# MCU_RF.net
KiCad netlist of a schematic drawn in Altium Designer
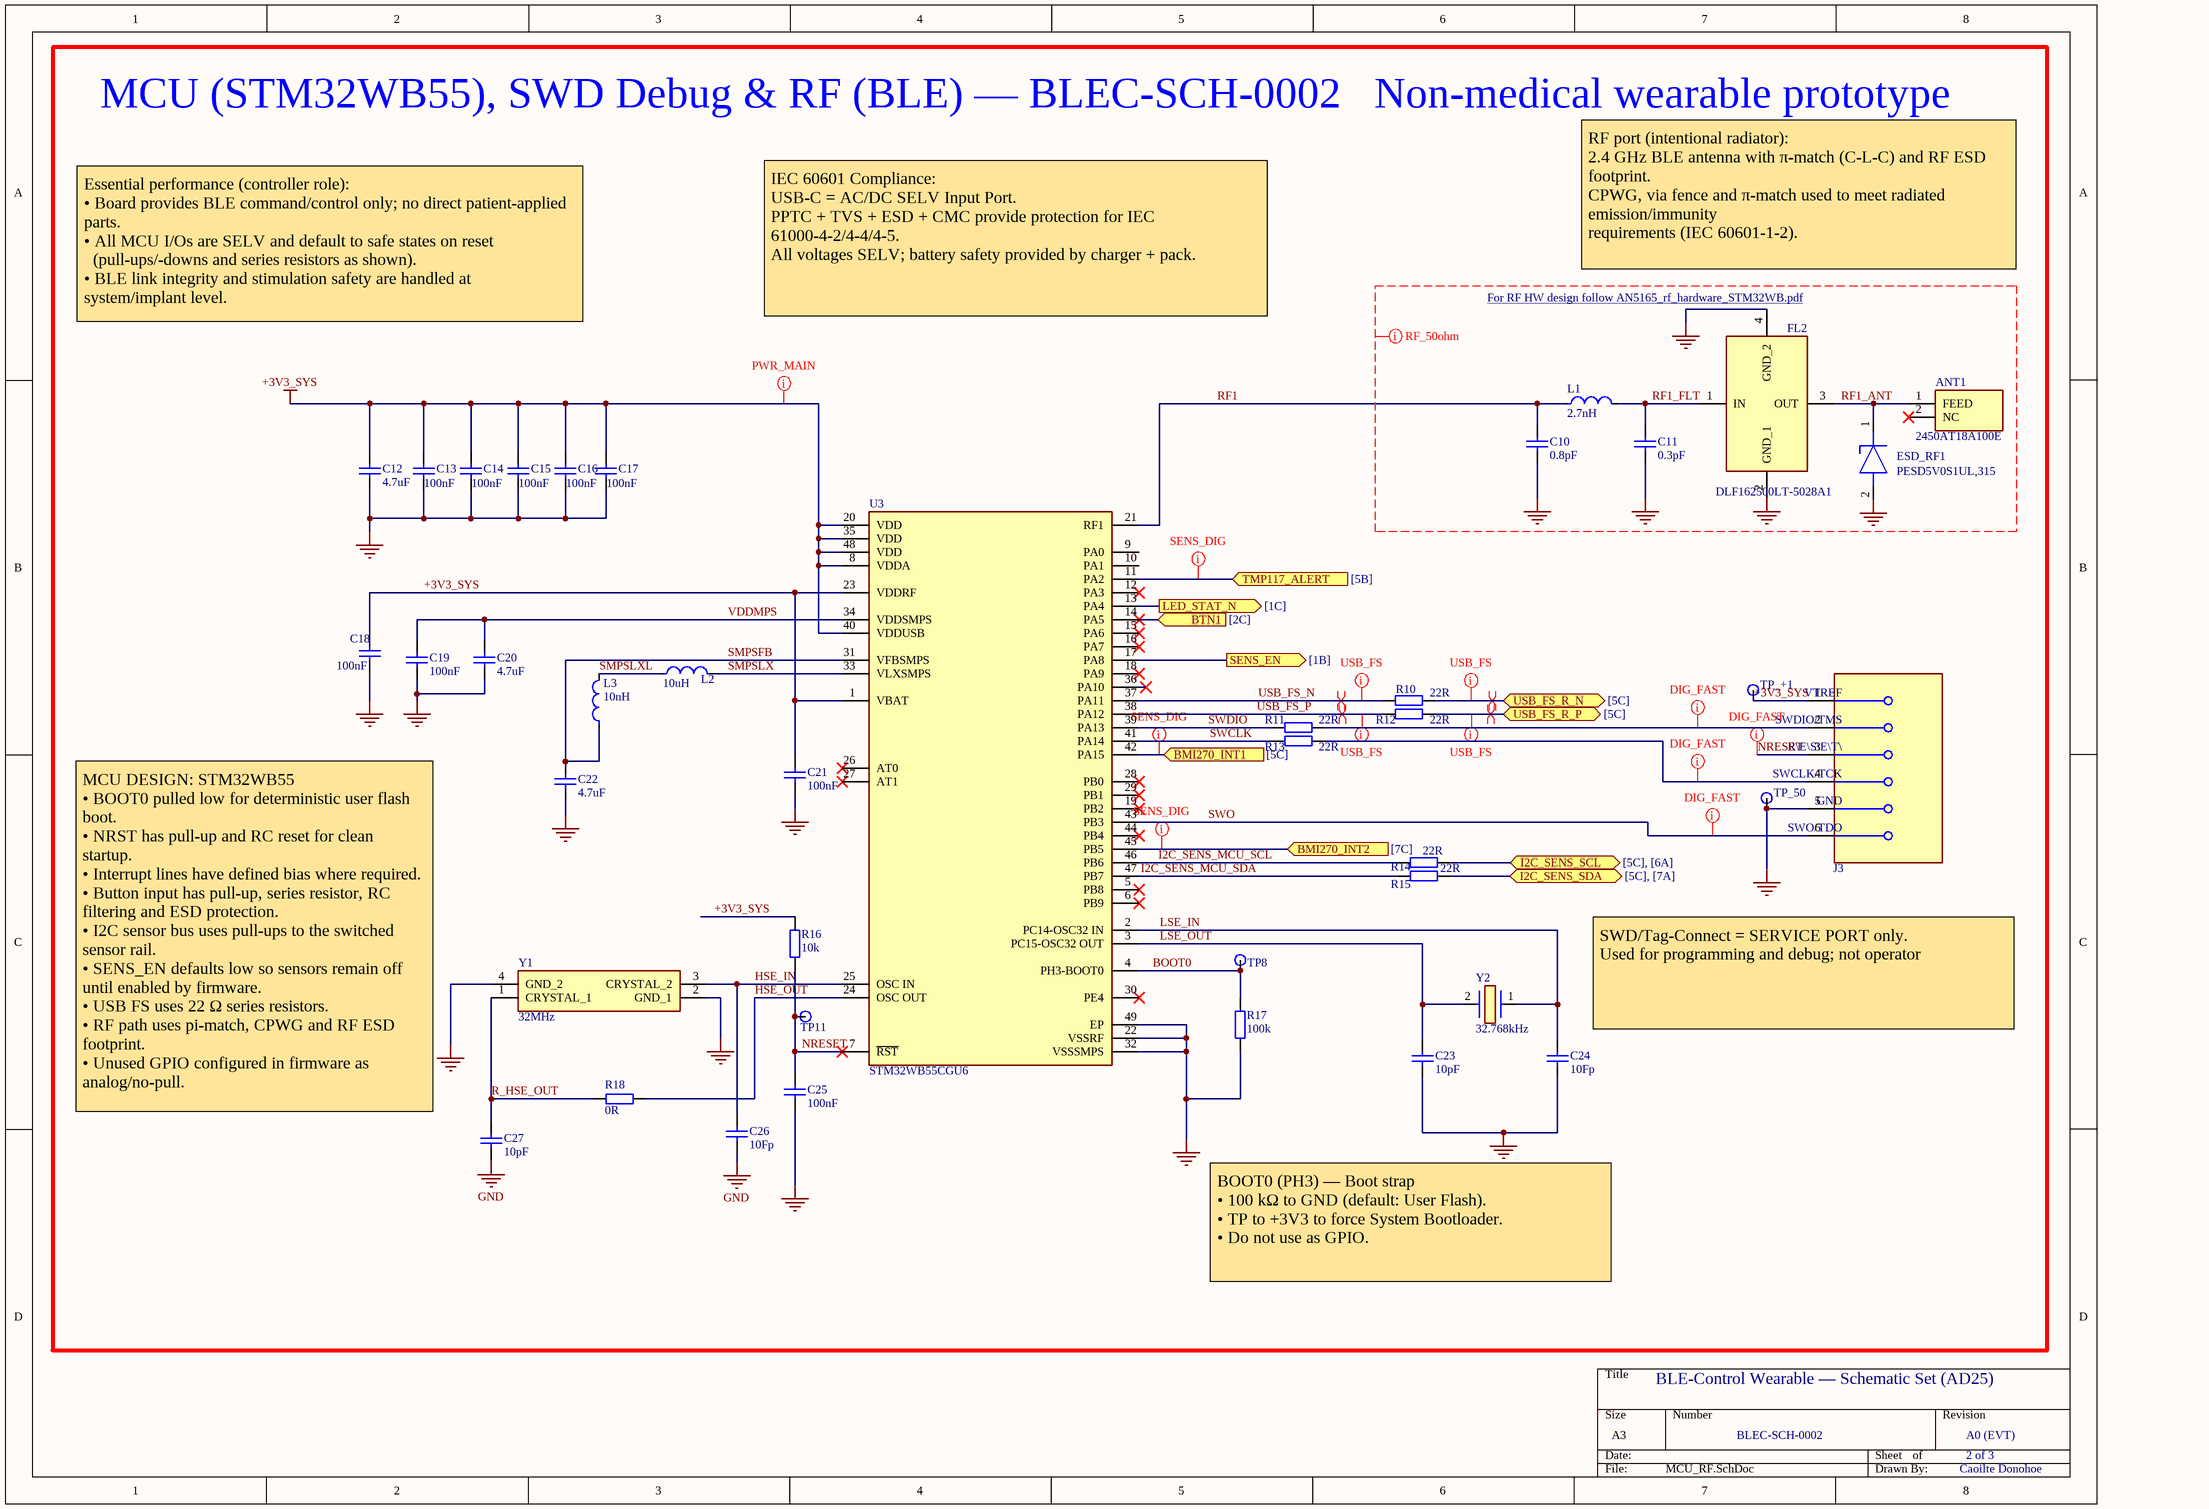
[diagram p0: MCU_RF.SchDoc]

(export (version "E")
  (design (tool "Eeschema 10.0.6"))
  (components
    (comp (ref "ANT1")
      (value "2450AT18A100E")
      (footprint "SamacSys:ANTC3216X140N")
      (description "Antenna")
      (fields (field (name "MOUSER PART NUMBER") "609-2450AT18A100E"))
      (libsource (lib "BLE-Control") (part "2450AT18A100E"))
    )
    (comp (ref "C10")
      (value "0.8pF")
      (footprint "CAP_0402")
      (description "GRM1555C1HR80BA01D")
      (fields (field (name "VOLTAGE") "10V") (field (name "TOLERANCE") "10%"))
      (libsource (lib "BLE-Control") (part "C_0402"))
    )
    (comp (ref "C11")
      (value "0.3pF")
      (footprint "CAP_0402")
      (description "GRM1555C1HR30WA01D")
      (fields (field (name "VOLTAGE") "10V") (field (name "TOLERANCE") "10%"))
      (libsource (lib "BLE-Control") (part "C_0402"))
    )
    (comp (ref "C12")
      (value "4.7uF")
      (footprint "CAP_0402")
      (description "Ceramic Chip Capacitor 0402")
      (fields (field (name "VOLTAGE") "10V") (field (name "TOLERANCE") "10%"))
      (libsource (lib "BLE-Control") (part "C_0402"))
    )
    (comp (ref "C13")
      (value "100nF")
      (footprint "CAP_0402")
      (description "Ceramic Chip Capacitor 0402")
      (fields (field (name "VOLTAGE") "10V") (field (name "TOLERANCE") "10%"))
      (libsource (lib "BLE-Control") (part "C_0402"))
    )
    (comp (ref "C14")
      (value "100nF")
      (footprint "CAP_0402")
      (description "Ceramic Chip Capacitor 0402")
      (fields (field (name "VOLTAGE") "10V") (field (name "TOLERANCE") "10%"))
      (libsource (lib "BLE-Control") (part "C_0402"))
    )
    (comp (ref "C15")
      (value "100nF")
      (footprint "CAP_0402")
      (description "Ceramic Chip Capacitor 0402")
      (fields (field (name "VOLTAGE") "10V") (field (name "TOLERANCE") "10%"))
      (libsource (lib "BLE-Control") (part "C_0402"))
    )
    (comp (ref "C16")
      (value "100nF")
      (footprint "CAP_0402")
      (description "Ceramic Chip Capacitor 0402")
      (fields (field (name "VOLTAGE") "10V") (field (name "TOLERANCE") "10%"))
      (libsource (lib "BLE-Control") (part "C_0402"))
    )
    (comp (ref "C17")
      (value "100nF")
      (footprint "CAP_0402")
      (description "Ceramic Chip Capacitor 0402")
      (fields (field (name "VOLTAGE") "10V") (field (name "TOLERANCE") "10%"))
      (libsource (lib "BLE-Control") (part "C_0402"))
    )
    (comp (ref "C18")
      (value "100nF")
      (footprint "CAP_0402")
      (description "Ceramic Chip Capacitor 0402")
      (fields (field (name "VOLTAGE") "10V") (field (name "TOLERANCE") "10%"))
      (libsource (lib "BLE-Control") (part "C_0402"))
    )
    (comp (ref "C19")
      (value "100nF")
      (footprint "CAP_0402")
      (description "Ceramic Chip Capacitor 0402")
      (fields (field (name "VOLTAGE") "10V") (field (name "TOLERANCE") "10%"))
      (libsource (lib "BLE-Control") (part "C_0402"))
    )
    (comp (ref "C20")
      (value "4.7uF")
      (footprint "CAP_0402")
      (description "Ceramic Chip Capacitor 0402")
      (fields (field (name "VOLTAGE") "10V") (field (name "TOLERANCE") "10%"))
      (libsource (lib "BLE-Control") (part "C_0402"))
    )
    (comp (ref "C21")
      (value "100nF")
      (footprint "CAP_0402")
      (description "Ceramic Chip Capacitor 0402")
      (fields (field (name "VOLTAGE") "10V") (field (name "TOLERANCE") "10%"))
      (libsource (lib "BLE-Control") (part "C_0402"))
    )
    (comp (ref "C22")
      (value "4.7uF")
      (footprint "CAP_0402")
      (description "Ceramic Chip Capacitor 0402")
      (fields (field (name "VOLTAGE") "10V") (field (name "TOLERANCE") "10%"))
      (libsource (lib "BLE-Control") (part "C_0402"))
    )
    (comp (ref "C23")
      (value "10pF")
      (footprint "CAP_0402")
      (description "Ceramic Chip Capacitor 0402")
      (fields (field (name "VOLTAGE") "10V") (field (name "TOLERANCE") "10%"))
      (libsource (lib "BLE-Control") (part "C_0402"))
    )
    (comp (ref "C24")
      (value "10Fp")
      (footprint "CAP_0402")
      (description "Ceramic Chip Capacitor 0402")
      (fields (field (name "VOLTAGE") "10V") (field (name "TOLERANCE") "10%"))
      (libsource (lib "BLE-Control") (part "C_0402"))
    )
    (comp (ref "C25")
      (value "100nF")
      (footprint "CAP_0402")
      (description "Ceramic Chip Capacitor 0402")
      (fields (field (name "VOLTAGE") "10V") (field (name "TOLERANCE") "10%"))
      (libsource (lib "BLE-Control") (part "C_0402"))
    )
    (comp (ref "C26")
      (value "10Fp")
      (footprint "CAP_0402")
      (description "Ceramic Chip Capacitor 0402")
      (fields (field (name "VOLTAGE") "10V") (field (name "TOLERANCE") "10%"))
      (libsource (lib "BLE-Control") (part "C_0402"))
    )
    (comp (ref "C27")
      (value "10pF")
      (footprint "CAP_0402")
      (description "Ceramic Chip Capacitor 0402")
      (fields (field (name "VOLTAGE") "10V") (field (name "TOLERANCE") "10%"))
      (libsource (lib "BLE-Control") (part "C_0402"))
    )
    (comp (ref "ESD_RF1")
      (value "PESD5V0S1UL,315")
      (footprint "PESD5V0S1BL315")
      (description "Diode ESD (Uni-directional)")
      (fields (field (name "MOUSER PART NUMBER") "771-PESD5V0S1UL315"))
      (libsource (lib "*") (part "PESD5V0S1UL,315"))
    )
    (comp (ref "FL2")
      (value "DLF162500LT-5028A1")
      (footprint "DLF162500LT5028A1 - duplicate")
      (description "Filter")
      (fields (field (name "MOUSER PART NUMBER") "810-DLF16250LT5028A1"))
      (libsource (lib "BLE-Control") (part "DLF162500LT-5028A1"))
    )
    (comp (ref "J3")
      (value "TC2030-CTX-NL")
      (footprint "Tag_Connect_0_MFG")
      (libsource (lib "BLE-Control") (part "TC2030-CTX-NL"))
    )
    (comp (ref "L1")
      (value "2.7nH")
      (footprint "FP-LQW15AN_00-W0_6-0_1-MFG")
      (description "Wire Wound RF Inductor 10nH ±2% 500mA 0.17Ω 0402 (1005)")
      (fields (field (name "TOLERANCE") "2%"))
      (libsource (lib "BLE-Control") (part "CMP-06042-002082-1"))
    )
    (comp (ref "L2")
      (value "10uH")
      (footprint "FP-LQM21FN_70-IPC_B")
      (description "FIXED IND 10UH 100MA 780MOHM SMD")
      (fields (field (name "TOLERANCE") "20%"))
      (libsource (lib "BLE-Control") (part "CMP-2000-06587-2"))
    )
    (comp (ref "L3")
      (value "10nH")
      (footprint "FP-LQW15AN_00-W0_6-0_1-MFG")
      (description "LQG15HS2N7S02")
      (fields (field (name "TOLERANCE") "2%"))
      (libsource (lib "BLE-Control") (part "CMP-06042-002082-1"))
    )
    (comp (ref "R10")
      (value "22R")
      (footprint "RES_0402")
      (description "Resistor SMD 0402")
      (libsource (lib "BLE-Control") (part "R_0402"))
    )
    (comp (ref "R11")
      (value "22R")
      (footprint "RES_0402")
      (description "Resistor SMD 0402")
      (libsource (lib "BLE-Control") (part "R_0402"))
    )
    (comp (ref "R12")
      (value "22R")
      (footprint "RES_0402")
      (description "Resistor SMD 0402")
      (libsource (lib "BLE-Control") (part "R_0402"))
    )
    (comp (ref "R13")
      (value "22R")
      (footprint "RES_0402")
      (description "Resistor SMD 0402")
      (libsource (lib "BLE-Control") (part "R_0402"))
    )
    (comp (ref "R14")
      (value "22R")
      (footprint "RES_0402")
      (description "Resistor SMD 0402")
      (libsource (lib "BLE-Control") (part "R_0402"))
    )
    (comp (ref "R15")
      (value "22R")
      (footprint "RES_0402")
      (description "Resistor SMD 0402")
      (libsource (lib "BLE-Control") (part "R_0402"))
    )
    (comp (ref "R16")
      (value "10k")
      (footprint "RES_0402")
      (description "Resistor SMD 0402")
      (libsource (lib "BLE-Control") (part "R_0402"))
    )
    (comp (ref "R17")
      (value "100k")
      (footprint "RES_0402")
      (description "Resistor SMD 0402")
      (libsource (lib "BLE-Control") (part "R_0402"))
    )
    (comp (ref "R18")
      (value "0R")
      (footprint "RES_0402")
      (description "Resistor SMD 0402")
      (libsource (lib "BLE-Control") (part "R_0402"))
    )
    (comp (ref "TP8")
      (value "TestPoint")
      (footprint "PCBComponent_1")
      (libsource (lib "BLE-Control") (part "TestPoint"))
    )
    (comp (ref "TP11")
      (value "TestPoint")
      (footprint "PCBComponent_1")
      (libsource (lib "BLE-Control") (part "TestPoint"))
    )
    (comp (ref "TP_+1")
      (value "TP_+3V3_SYS")
      (footprint "TP_VIA_0p75")
      (libsource (lib "BLE-Control") (part "TestPoint"))
    )
    (comp (ref "TP_50")
      (value "TestPoint")
      (footprint "TP_VIA_0p75")
      (libsource (lib "BLE-Control") (part "TestPoint"))
    )
    (comp (ref "U3")
      (value "STM32WB55CGU6")
      (footprint "FP-STM32WB55CGU6-IPC_C")
      (description "ULTRA-LOW-POWER DUAL CORE ARM CO")
      (fields
        (field (name "OCTOPART") "https://octopart.com/stm32wb55cgu6-stmicroelectronics-98750847")
        (field (name "MANUFACTURER") "STMicroelectronics")
      )
      (libsource (lib "BLE-Control") (part "CMP-12105-000013-1"))
    )
    (comp (ref "Y1")
      (value "32MHz")
      (footprint "SamacSys:NX3225SA32MHZEXS00ACS02368")
      (description "Crystal or Oscillator")
      (fields
        (field (name "MANUFACTURER_PART_NUMBER") "NX3225SA-32MHZ-EXS00A-CS02368")
        (field (name "MOUSER PART NUMBER") "344-NX3225SA32MHZEXS")
      )
      (libsource (lib "*") (part "NX3225SA-32MHZ-EXS00A-CS02368"))
    )
    (comp (ref "Y2")
      (value "32.768kHz")
      (footprint "SamacSys:ABS07")
      (description "Crystal or Oscillator")
      (fields
        (field (name "MANUFACTURER_PART_NUMBER") "ABS07-32.768KHZ-7-T")
        (field (name "MOUSER PART NUMBER") "815-ABS07-32.768K7T")
      )
      (libsource (lib "*") (part "ABS07-32.768KHZ-7-T"))
    )
  )
  (nets
    (net (code "1") (name "+3V3_SYS") (class "Default")
      (node (ref "C12") (pin "2") (pinfunction "2_2") (pintype "passive"))
      (node (ref "C13") (pin "2") (pinfunction "2_2") (pintype "passive"))
      (node (ref "C14") (pin "2") (pinfunction "2_2") (pintype "passive"))
      (node (ref "C15") (pin "2") (pinfunction "2_2") (pintype "passive"))
      (node (ref "C16") (pin "2") (pinfunction "2_2") (pintype "passive"))
      (node (ref "C17") (pin "2") (pinfunction "2_2") (pintype "passive"))
      (node (ref "C18") (pin "2") (pinfunction "2_2") (pintype "passive"))
      (node (ref "C21") (pin "2") (pinfunction "2_2") (pintype "passive"))
      (node (ref "J3") (pin "1") (pinfunction "VTREF_1") (pintype "passive"))
      (node (ref "R16") (pin "2") (pinfunction "2_2") (pintype "passive"))
      (node (ref "TP_+1") (pin "1") (pinfunction "0_1") (pintype "passive"))
      (node (ref "U3") (pin "1") (pinfunction "VBAT_1") (pintype "passive"))
      (node (ref "U3") (pin "20") (pinfunction "VDD_20") (pintype "passive"))
      (node (ref "U3") (pin "23") (pinfunction "VDDRF_23") (pintype "passive"))
      (node (ref "U3") (pin "35") (pinfunction "VDD_35") (pintype "passive"))
      (node (ref "U3") (pin "40") (pinfunction "VDDUSB_40") (pintype "passive"))
      (node (ref "U3") (pin "48") (pinfunction "VDD_48") (pintype "passive"))
      (node (ref "U3") (pin "8") (pinfunction "VDDA_8") (pintype "passive"))
    )
    (net (code "2") (name "/BMI270_INT1") (class "Default")
      (node (ref "U3") (pin "42") (pinfunction "PA15_42") (pintype "passive"))
    )
    (net (code "3") (name "/BMI270_INT2") (class "Default")
      (node (ref "U3") (pin "45") (pinfunction "PB5_45") (pintype "passive"))
    )
    (net (code "4") (name "/BOOT0") (class "Default")
      (node (ref "R17") (pin "2") (pinfunction "2_2") (pintype "passive"))
      (node (ref "TP8") (pin "1") (pinfunction "0_1") (pintype "passive"))
      (node (ref "U3") (pin "4") (pinfunction "PH3-BOOT0_4") (pintype "passive"))
    )
    (net (code "5") (name "/BTN1") (class "Default")
      (node (ref "U3") (pin "14") (pinfunction "PA5_14") (pintype "passive+no_connect"))
    )
    (net (code "6") (name "/HSE_IN") (class "Default")
      (node (ref "C26") (pin "2") (pinfunction "2_2") (pintype "passive"))
      (node (ref "U3") (pin "25") (pinfunction "OSC_IN_25") (pintype "passive"))
      (node (ref "Y1") (pin "3") (pinfunction "CRYSTAL_2_3") (pintype "passive"))
    )
    (net (code "7") (name "/HSE_OUT") (class "Default")
      (node (ref "R18") (pin "2") (pinfunction "2_2") (pintype "passive"))
      (node (ref "U3") (pin "24") (pinfunction "OSC_OUT_24") (pintype "passive"))
    )
    (net (code "8") (name "/I2C_SENS_MCU_SCL") (class "Default")
      (node (ref "R14") (pin "1") (pinfunction "1_1") (pintype "passive"))
      (node (ref "U3") (pin "46") (pinfunction "PB6_46") (pintype "passive"))
    )
    (net (code "9") (name "/I2C_SENS_MCU_SDA") (class "Default")
      (node (ref "R15") (pin "1") (pinfunction "1_1") (pintype "passive"))
      (node (ref "U3") (pin "47") (pinfunction "PB7_47") (pintype "passive"))
    )
    (net (code "10") (name "/I2C_SENS_SCL") (class "Default")
      (node (ref "R14") (pin "2") (pinfunction "2_2") (pintype "passive"))
    )
    (net (code "11") (name "/I2C_SENS_SDA") (class "Default")
      (node (ref "R15") (pin "2") (pinfunction "2_2") (pintype "passive"))
    )
    (net (code "12") (name "/LED_STAT_N") (class "Default")
      (node (ref "U3") (pin "13") (pinfunction "PA4_13") (pintype "passive"))
    )
    (net (code "13") (name "/LSE_IN") (class "Default")
      (node (ref "C24") (pin "2") (pinfunction "2_2") (pintype "passive"))
      (node (ref "U3") (pin "2") (pinfunction "PC14-OSC32_IN_2") (pintype "passive"))
      (node (ref "Y2") (pin "1") (pinfunction "1_1") (pintype "passive"))
    )
    (net (code "14") (name "/LSE_OUT") (class "Default")
      (node (ref "C23") (pin "2") (pinfunction "2_2") (pintype "passive"))
      (node (ref "U3") (pin "3") (pinfunction "PC15-OSC32_OUT_3") (pintype "passive"))
      (node (ref "Y2") (pin "2") (pinfunction "2_2") (pintype "passive"))
    )
    (net (code "15") (name "/NRESET") (class "Default")
      (node (ref "C25") (pin "2") (pinfunction "2_2") (pintype "passive"))
      (node (ref "J3") (pin "3") (pinfunction "~{RESET}_3") (pintype "passive"))
      (node (ref "R16") (pin "1") (pinfunction "1_1") (pintype "passive"))
      (node (ref "TP11") (pin "1") (pinfunction "0_1") (pintype "passive"))
      (node (ref "U3") (pin "7") (pinfunction "~{RST}_7") (pintype "passive"))
    )
    (net (code "16") (name "/RF1") (class "Default")
      (node (ref "C10") (pin "2") (pinfunction "2_2") (pintype "passive"))
      (node (ref "L1") (pin "1") (pinfunction "1_1") (pintype "passive"))
      (node (ref "U3") (pin "21") (pinfunction "RF1_21") (pintype "passive"))
    )
    (net (code "17") (name "/RF1_ANT") (class "Default")
      (node (ref "ANT1") (pin "1") (pinfunction "FEED_1") (pintype "passive"))
      (node (ref "ESD_RF1") (pin "1") (pinfunction "K_1") (pintype "passive"))
      (node (ref "FL2") (pin "3") (pinfunction "OUT_3") (pintype "passive"))
    )
    (net (code "18") (name "/RF1_FLT") (class "Default")
      (node (ref "C11") (pin "2") (pinfunction "2_2") (pintype "passive"))
      (node (ref "FL2") (pin "1") (pinfunction "IN_1") (pintype "passive"))
      (node (ref "L1") (pin "2") (pinfunction "2_2") (pintype "passive"))
    )
    (net (code "19") (name "/R_HSE_OUT") (class "Default")
      (node (ref "C27") (pin "2") (pinfunction "2_2") (pintype "passive"))
      (node (ref "R18") (pin "1") (pinfunction "1_1") (pintype "passive"))
      (node (ref "Y1") (pin "1") (pinfunction "CRYSTAL_1_1") (pintype "passive"))
    )
    (net (code "20") (name "/SENS_EN") (class "Default")
      (node (ref "U3") (pin "17") (pinfunction "PA8_17") (pintype "passive"))
    )
    (net (code "21") (name "/SMPSFB") (class "Default")
      (node (ref "C22") (pin "2") (pinfunction "2_2") (pintype "passive"))
      (node (ref "L3") (pin "1") (pinfunction "1_1") (pintype "passive"))
      (node (ref "U3") (pin "31") (pinfunction "VFBSMPS_31") (pintype "passive"))
    )
    (net (code "22") (name "/SMPSLX") (class "Default")
      (node (ref "L2") (pin "2") (pinfunction "2_2") (pintype "passive"))
      (node (ref "U3") (pin "33") (pinfunction "VLXSMPS_33") (pintype "passive"))
    )
    (net (code "23") (name "/SMPSLXL") (class "Default")
      (node (ref "L2") (pin "1") (pinfunction "1_1") (pintype "passive"))
      (node (ref "L3") (pin "2") (pinfunction "2_2") (pintype "passive"))
    )
    (net (code "24") (name "/SWCLK") (class "Default")
      (node (ref "R13") (pin "1") (pinfunction "1_1") (pintype "passive"))
      (node (ref "U3") (pin "41") (pinfunction "PA14_41") (pintype "passive"))
    )
    (net (code "25") (name "/SWDIO") (class "Default")
      (node (ref "R11") (pin "1") (pinfunction "1_1") (pintype "passive"))
      (node (ref "U3") (pin "39") (pinfunction "PA13_39") (pintype "passive"))
    )
    (net (code "26") (name "/SWO") (class "Default")
      (node (ref "J3") (pin "6") (pinfunction "SWO/TDO_6") (pintype "passive"))
      (node (ref "U3") (pin "43") (pinfunction "PB3_43") (pintype "passive"))
    )
    (net (code "27") (name "/TMP117_ALERT") (class "Default")
      (node (ref "U3") (pin "11") (pinfunction "PA2_11") (pintype "passive"))
    )
    (net (code "28") (name "/USB_FS_N") (class "Default")
      (node (ref "R10") (pin "1") (pinfunction "1_1") (pintype "passive"))
      (node (ref "U3") (pin "37") (pinfunction "PA11_37") (pintype "passive"))
    )
    (net (code "29") (name "/USB_FS_P") (class "Default")
      (node (ref "R12") (pin "1") (pinfunction "1_1") (pintype "passive"))
      (node (ref "U3") (pin "38") (pinfunction "PA12_38") (pintype "passive"))
    )
    (net (code "30") (name "/USB_FS_R_N") (class "Default")
      (node (ref "R10") (pin "2") (pinfunction "2_2") (pintype "passive"))
    )
    (net (code "31") (name "/USB_FS_R_P") (class "Default")
      (node (ref "R12") (pin "2") (pinfunction "2_2") (pintype "passive"))
    )
    (net (code "32") (name "/VDDMPS") (class "Default")
      (node (ref "C19") (pin "2") (pinfunction "2_2") (pintype "passive"))
      (node (ref "C20") (pin "2") (pinfunction "2_2") (pintype "passive"))
      (node (ref "U3") (pin "34") (pinfunction "VDDSMPS_34") (pintype "passive"))
    )
    (net (code "33") (name "GND") (class "Default")
      (node (ref "C10") (pin "1") (pinfunction "1_1") (pintype "passive"))
      (node (ref "C11") (pin "1") (pinfunction "1_1") (pintype "passive"))
      (node (ref "C12") (pin "1") (pinfunction "1_1") (pintype "passive"))
      (node (ref "C13") (pin "1") (pinfunction "1_1") (pintype "passive"))
      (node (ref "C14") (pin "1") (pinfunction "1_1") (pintype "passive"))
      (node (ref "C15") (pin "1") (pinfunction "1_1") (pintype "passive"))
      (node (ref "C16") (pin "1") (pinfunction "1_1") (pintype "passive"))
      (node (ref "C17") (pin "1") (pinfunction "1_1") (pintype "passive"))
      (node (ref "C18") (pin "1") (pinfunction "1_1") (pintype "passive"))
      (node (ref "C19") (pin "1") (pinfunction "1_1") (pintype "passive"))
      (node (ref "C20") (pin "1") (pinfunction "1_1") (pintype "passive"))
      (node (ref "C21") (pin "1") (pinfunction "1_1") (pintype "passive"))
      (node (ref "C22") (pin "1") (pinfunction "1_1") (pintype "passive"))
      (node (ref "C23") (pin "1") (pinfunction "1_1") (pintype "passive"))
      (node (ref "C24") (pin "1") (pinfunction "1_1") (pintype "passive"))
      (node (ref "C25") (pin "1") (pinfunction "1_1") (pintype "passive"))
      (node (ref "C26") (pin "1") (pinfunction "1_1") (pintype "passive"))
      (node (ref "C27") (pin "1") (pinfunction "1_1") (pintype "passive"))
      (node (ref "ESD_RF1") (pin "2") (pinfunction "A_2") (pintype "passive"))
      (node (ref "FL2") (pin "2") (pinfunction "GND_1_2") (pintype "passive"))
      (node (ref "FL2") (pin "4") (pinfunction "GND_2_4") (pintype "passive"))
      (node (ref "J3") (pin "5") (pinfunction "GND_5") (pintype "passive"))
      (node (ref "R17") (pin "1") (pinfunction "1_1") (pintype "passive"))
      (node (ref "TP_50") (pin "1") (pinfunction "0_1") (pintype "passive"))
      (node (ref "U3") (pin "22") (pinfunction "VSSRF_22") (pintype "passive"))
      (node (ref "U3") (pin "32") (pinfunction "VSSSMPS_32") (pintype "passive"))
      (node (ref "U3") (pin "49") (pinfunction "EP_49") (pintype "power_in"))
      (node (ref "Y1") (pin "2") (pinfunction "GND_1_2") (pintype "passive"))
      (node (ref "Y1") (pin "4") (pinfunction "GND_2_4") (pintype "passive"))
    )
    (net (code "34") (name "Net-(J3-SWCLK{slash}TCK)") (class "Default")
      (node (ref "J3") (pin "4") (pinfunction "SWCLK/TCK_4") (pintype "passive"))
      (node (ref "R13") (pin "2") (pinfunction "2_2") (pintype "passive"))
    )
    (net (code "35") (name "Net-(J3-SWDIO{slash}TMS)") (class "Default")
      (node (ref "J3") (pin "2") (pinfunction "SWDIO/TMS_2") (pintype "passive"))
      (node (ref "R11") (pin "2") (pinfunction "2_2") (pintype "passive"))
    )
    (net (code "36") (name "unconnected-(ANT1-NC-Pad2)") (class "Default")
      (node (ref "ANT1") (pin "2") (pinfunction "NC_2") (pintype "passive+no_connect"))
    )
    (net (code "37") (name "unconnected-(U3-AT0-Pad26)") (class "Default")
      (node (ref "U3") (pin "26") (pinfunction "AT0_26") (pintype "passive+no_connect"))
    )
    (net (code "38") (name "unconnected-(U3-AT1-Pad27)") (class "Default")
      (node (ref "U3") (pin "27") (pinfunction "AT1_27") (pintype "passive+no_connect"))
    )
    (net (code "39") (name "unconnected-(U3-PA0-Pad9)") (class "Default")
      (node (ref "U3") (pin "9") (pinfunction "PA0_9") (pintype "passive"))
    )
    (net (code "40") (name "unconnected-(U3-PA1-Pad10)") (class "Default")
      (node (ref "U3") (pin "10") (pinfunction "PA1_10") (pintype "passive"))
    )
    (net (code "41") (name "unconnected-(U3-PA3-Pad12)") (class "Default")
      (node (ref "U3") (pin "12") (pinfunction "PA3_12") (pintype "passive+no_connect"))
    )
    (net (code "42") (name "unconnected-(U3-PA6-Pad15)") (class "Default")
      (node (ref "U3") (pin "15") (pinfunction "PA6_15") (pintype "passive+no_connect"))
    )
    (net (code "43") (name "unconnected-(U3-PA7-Pad16)") (class "Default")
      (node (ref "U3") (pin "16") (pinfunction "PA7_16") (pintype "passive+no_connect"))
    )
    (net (code "44") (name "unconnected-(U3-PA9-Pad18)") (class "Default")
      (node (ref "U3") (pin "18") (pinfunction "PA9_18") (pintype "passive+no_connect"))
    )
    (net (code "45") (name "unconnected-(U3-PA10-Pad36)") (class "Default")
      (node (ref "U3") (pin "36") (pinfunction "PA10_36") (pintype "passive+no_connect"))
    )
    (net (code "46") (name "unconnected-(U3-PB0-Pad28)") (class "Default")
      (node (ref "U3") (pin "28") (pinfunction "PB0_28") (pintype "passive+no_connect"))
    )
    (net (code "47") (name "unconnected-(U3-PB1-Pad29)") (class "Default")
      (node (ref "U3") (pin "29") (pinfunction "PB1_29") (pintype "passive+no_connect"))
    )
    (net (code "48") (name "unconnected-(U3-PB2-Pad19)") (class "Default")
      (node (ref "U3") (pin "19") (pinfunction "PB2_19") (pintype "passive+no_connect"))
    )
    (net (code "49") (name "unconnected-(U3-PB4-Pad44)") (class "Default")
      (node (ref "U3") (pin "44") (pinfunction "PB4_44") (pintype "passive+no_connect"))
    )
    (net (code "50") (name "unconnected-(U3-PB8-Pad5)") (class "Default")
      (node (ref "U3") (pin "5") (pinfunction "PB8_5") (pintype "passive+no_connect"))
    )
    (net (code "51") (name "unconnected-(U3-PB9-Pad6)") (class "Default")
      (node (ref "U3") (pin "6") (pinfunction "PB9_6") (pintype "passive+no_connect"))
    )
    (net (code "52") (name "unconnected-(U3-PE4-Pad30)") (class "Default")
      (node (ref "U3") (pin "30") (pinfunction "PE4_30") (pintype "passive+no_connect"))
    )
  )
)
